# 464414_22-01_Sheet1.net
KiCad netlist of a schematic drawn in Altium Designer
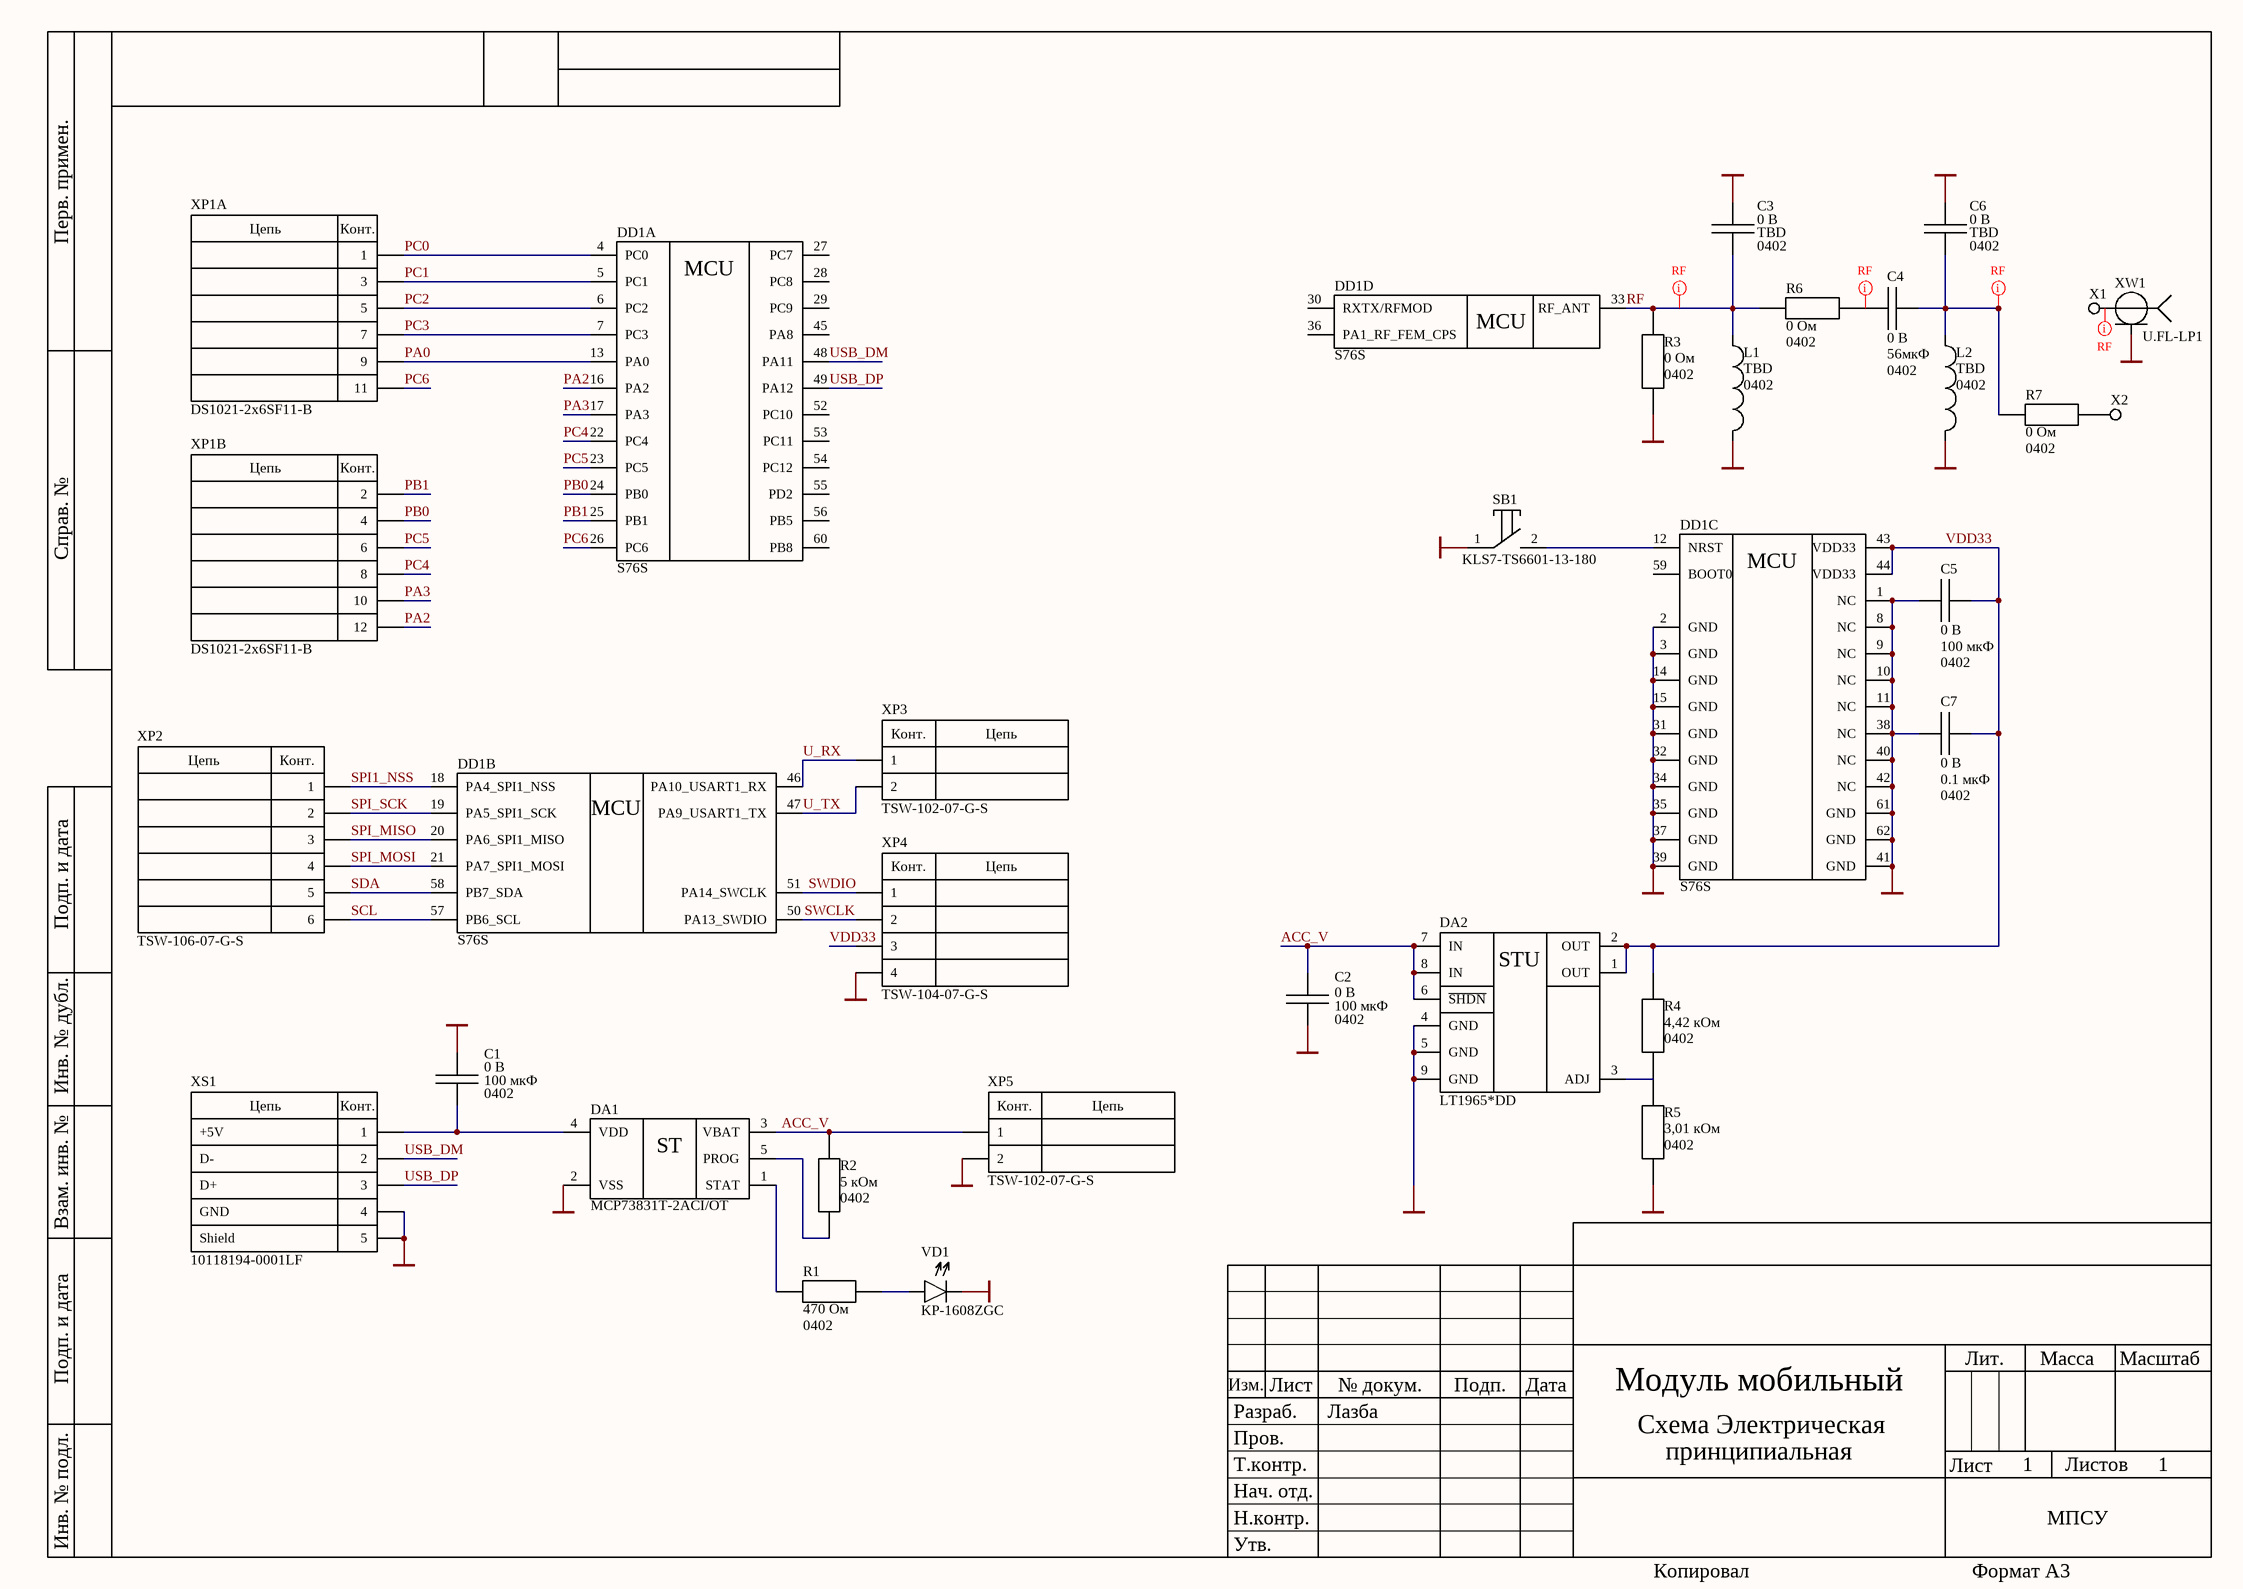
[diagram p0: МПСУ.464414.22-01 Sheet1.SchDoc]

(export (version "E")
  (design (tool "Eeschema 10.0.6"))
  (components
    (comp (ref "C1")
      (value "100 мкФ")
      (footprint "Passive_V2_0:CAPC100X50X55L20N")
      (description "Capacitor 0402")
      (fields
        (field (name "TOLERANCE") "0 %")
        (field (name "PEAK_CONDITION") "0 В")
        (field (name "PACKAGE") "0402")
        (field (name "Comment") "100 мкФ ± 0 % 0 В  0402 ")
        (field (name "DESIGNER") "Свидерский")
      )
      (libsource (lib "Passive_V2_0") (part "C 0402"))
    )
    (comp (ref "C2")
      (value "100 мкФ")
      (footprint "Passive_V2_0:CAPC100X50X55L20N")
      (description "Capacitor 0402")
      (fields
        (field (name "TOLERANCE") "0 %")
        (field (name "PEAK_CONDITION") "0 В")
        (field (name "PACKAGE") "0402")
        (field (name "Comment") "100 мкФ ± 0 % 0 В  0402 ")
        (field (name "DESIGNER") "Свидерский")
      )
      (libsource (lib "Passive_V2_0") (part "C 0402"))
    )
    (comp (ref "C3")
      (value "TBD")
      (footprint "Passive_V2_0:CAPC100X50X55L20N")
      (description "Capacitor 0402")
      (fields
        (field (name "TOLERANCE") "0 %")
        (field (name "PEAK_CONDITION") "0 В")
        (field (name "PACKAGE") "0402")
        (field (name "Comment") "TBD ± 0 % 0 В  0402 ")
        (field (name "DESIGNER") "Свидерский")
      )
      (libsource (lib "Passive_V2_0") (part "C 0402"))
    )
    (comp (ref "C4")
      (value "56мкФ")
      (footprint "Passive_V2_0:CAPC100X50X55L20N")
      (description "Capacitor 0402")
      (fields
        (field (name "TOLERANCE") "0 %")
        (field (name "PEAK_CONDITION") "0 В")
        (field (name "PACKAGE") "0402")
        (field (name "Comment") "56мкФ ± 0 % 0 В  0402 ")
        (field (name "DESIGNER") "Свидерский")
      )
      (libsource (lib "Passive_V2_0") (part "C 0402"))
    )
    (comp (ref "C5")
      (value "100 мкФ")
      (footprint "Passive_V2_0:CAPC100X50X55L20N")
      (description "Capacitor 0402")
      (fields
        (field (name "TOLERANCE") "0 %")
        (field (name "PEAK_CONDITION") "0 В")
        (field (name "PACKAGE") "0402")
        (field (name "Comment") "100 мкФ ± 0 % 0 В  0402 ")
        (field (name "DESIGNER") "Свидерский")
      )
      (libsource (lib "Passive_V2_0") (part "C 0402"))
    )
    (comp (ref "C6")
      (value "TBD")
      (footprint "Passive_V2_0:CAPC100X50X55L20N")
      (description "Capacitor 0402")
      (fields
        (field (name "TOLERANCE") "0 %")
        (field (name "PEAK_CONDITION") "0 В")
        (field (name "PACKAGE") "0402")
        (field (name "Comment") "TBD ± 0 % 0 В  0402 ")
        (field (name "DESIGNER") "Свидерский")
      )
      (libsource (lib "Passive_V2_0") (part "C 0402"))
    )
    (comp (ref "C7")
      (value "0.1 мкФ")
      (footprint "Passive_V2_0:CAPC100X50X55L20N")
      (description "Capacitor 0402")
      (fields
        (field (name "TOLERANCE") "0 %")
        (field (name "PEAK_CONDITION") "0 В")
        (field (name "PACKAGE") "0402")
        (field (name "Comment") "0.1 мкФ ± 0 % 0 В  0402 ")
        (field (name "DESIGNER") "Свидерский")
      )
      (libsource (lib "Passive_V2_0") (part "C 0402"))
    )
    (comp (ref "DA1")
      (value "MCP73831T-2ACI/OT")
      (footprint "IC_V2_0:SOTFL95P270X145-5N")
      (description "Miniature Single-Cell, Fully Integrated Li-Ion,\r\nLi-Polymer Charge Management Controllers")
      (fields
        (field (name "MANUFACTURER") "Microchip")
        (field (name "PARTNUMBER") "MCP73831T-2ACI/OT")
        (field (name "DESIGNER") "Лазба")
      )
      (libsource (lib "IC_V2_0") (part "MCP7383*"))
    )
    (comp (ref "DA2")
      (value "LT1965*DD")
      (footprint "IC_V2_0:SON9P50_300X300X80L40X25T244X160N")
      (description "1.1A, Low Noise,  Low Dropout Linear Regulator")
      (fields
        (field (name "MANUFACTURER") "Analog Devices")
        (field (name "PARTNUMBER") "LT1965*DD")
        (field (name "DESIGNER") "Свидерский")
      )
      (libsource (lib "IC_V2_0") (part "LT1965*DD"))
    )
    (comp (ref "DD1")
      (value "DD1")
      (footprint "IC_V2_0:S7XS")
      (fields
        (field (name "MANUFACTURER") "AcSIP")
        (field (name "PARTNUMBER") "S76S")
        (field (name "DESIGNER") "Лазба")
      )
      (libsource (lib "") (part "S76S_1"))
    )
    (comp (ref "L1")
      (value "TBD")
      (footprint "Passive_V2_0:INDC100X50X60L10N")
      (description "Inductor 0402")
      (fields
        (field (name "TOLERANCE") "0 %")
        (field (name "PACKAGE") "0402")
        (field (name "Comment") "TBD ± 0 % 0 А 0402 ")
        (field (name "DESIGNER") "Свидерский")
      )
      (libsource (lib "Passive_V2_0") (part "L 0402"))
    )
    (comp (ref "L2")
      (value "TBD")
      (footprint "Passive_V2_0:INDC100X50X60L10N")
      (description "Inductor 0402")
      (fields
        (field (name "TOLERANCE") "0 %")
        (field (name "PACKAGE") "0402")
        (field (name "Comment") "TBD ± 0 % 0 А 0402 ")
        (field (name "DESIGNER") "Свидерский")
      )
      (libsource (lib "Passive_V2_0") (part "L 0402"))
    )
    (comp (ref "R1")
      (value "470 Ом")
      (footprint "Passive_V2_0:RESC100X50X40L25N")
      (description "Resistor 0402")
      (fields
        (field (name "TOLERANCE") "0 %")
        (field (name "PACKAGE") "0402")
        (field (name "Comment") "470 Ом ± 0 % 0 Вт 0402 ")
        (field (name "DESIGNER") "Свидерский")
      )
      (libsource (lib "") (part "R 0402_1"))
    )
    (comp (ref "R2")
      (value "5 кОм")
      (footprint "Passive_V2_0:RESC100X50X40L25N")
      (description "Resistor 0402")
      (fields
        (field (name "TOLERANCE") "0 %")
        (field (name "PACKAGE") "0402")
        (field (name "Comment") "5 кОм ± 0 % 0 Вт 0402 ")
        (field (name "DESIGNER") "Свидерский")
      )
      (libsource (lib "") (part "R 0402_2"))
    )
    (comp (ref "R3")
      (value "0 Ом")
      (footprint "Passive_V2_0:RESC100X50X40L25N")
      (description "Resistor 0402")
      (fields
        (field (name "TOLERANCE") "0 %")
        (field (name "PACKAGE") "0402")
        (field (name "Comment") "0 Ом ± 0 % 0 Вт 0402 ")
        (field (name "DESIGNER") "Свидерский")
      )
      (libsource (lib "Passive_V2_0") (part "R 0402"))
    )
    (comp (ref "R4")
      (value "4,42 кОм")
      (footprint "Passive_V2_0:RESC100X50X40L25N")
      (description "Resistor 0402")
      (fields
        (field (name "TOLERANCE") "0 %")
        (field (name "PACKAGE") "0402")
        (field (name "Comment") "4,42 кОм ± 0 % 0 Вт 0402 ")
        (field (name "DESIGNER") "Свидерский")
      )
      (libsource (lib "Passive_V2_0") (part "R 0402"))
    )
    (comp (ref "R5")
      (value "3,01 кОм")
      (footprint "Passive_V2_0:RESC100X50X40L25N")
      (description "Resistor 0402")
      (fields
        (field (name "TOLERANCE") "0 %")
        (field (name "PACKAGE") "0402")
        (field (name "Comment") "3,01 кОм ± 0 % 0 Вт 0402 ")
        (field (name "DESIGNER") "Свидерский")
      )
      (libsource (lib "Passive_V2_0") (part "R 0402"))
    )
    (comp (ref "R6")
      (value "0 Ом")
      (footprint "Passive_V2_0:RESC100X50X40L25N")
      (description "Resistor 0402")
      (fields
        (field (name "TOLERANCE") "0 %")
        (field (name "PACKAGE") "0402")
        (field (name "Comment") "0 Ом ± 0 % 0 Вт 0402 ")
        (field (name "DESIGNER") "Свидерский")
      )
      (libsource (lib "") (part "R 0402_1"))
    )
    (comp (ref "R7")
      (value "0 Ом")
      (footprint "Passive_V2_0:RESC100X50X40L25N")
      (description "Resistor 0402")
      (fields
        (field (name "TOLERANCE") "0 %")
        (field (name "PACKAGE") "0402")
        (field (name "Comment") "0 Ом ± 0 % 0 Вт 0402 ")
        (field (name "DESIGNER") "Свидерский")
      )
      (libsource (lib "") (part "R 0402_1"))
    )
    (comp (ref "SB1")
      (value "~")
      (footprint "Passive_V2_0:KLS7-TS6601")
      (description "6x6 Tact Switch Series")
      (fields
        (field (name "MANUFACTURER") "KLS electronic co ltd")
        (field (name "PARTNUMBER") "KLS7-TS6601-13-180")
        (field (name "DESIGNER") "Лазба")
      )
      (libsource (lib "Passive_V2_0") (part "KLS7-TS6601*"))
    )
    (comp (ref "VD1")
      (value "KP-1608ZGC")
      (footprint "Discrete_V2_0:KP-1608ZGC")
      (description "1.6X0.8mm SMD CHIP LED LAMP")
      (fields
        (field (name "MANUFACTURER") "Kingbright")
        (field (name "PARTNUMBER") "KP-1608ZGC")
        (field (name "DESIGNER") "Ушакова")
      )
      (libsource (lib "Discrete_V2_0") (part "KP-1608***"))
    )
    (comp (ref "X1")
      (value "Contact Pad")
      (footprint "Primitive_V2_0:Contact_Pad 0.55x0.55")
      (description "Контактная площадка (1,5 х 1,5 мм) для запайки провода")
      (fields (field (name "DESIGNER") "Свидерский"))
      (libsource (lib "Primitive_V2_0") (part "Contact Pad"))
    )
    (comp (ref "X2")
      (value "Contact Pad")
      (footprint "Primitive_V2_0:Contact_Pad 0.55x0.55")
      (description "Контактная площадка (1,5 х 1,5 мм) для запайки провода")
      (fields (field (name "DESIGNER") "Свидерский"))
      (libsource (lib "Primitive_V2_0") (part "Contact Pad"))
    )
    (comp (ref "XP1")
      (value "DS1021-2x6SF11-B")
      (footprint "Connectors_V2_0:HDRV12W64P254_6X2_1524X508H600")
      (description "Вилка 2,54мм")
      (fields
        (field (name "MANUFACTURER") "Connfly Electronic")
        (field (name "PARTNUMBER") "DS1021-2x6SF11-B")
        (field (name "DESIGNER") "Свидерский")
      )
      (libsource (lib "Connectors_V2_0") (part "DS1021-2x6SF11-B"))
    )
    (comp (ref "XP2")
      (value "TSW-106-07-G-S")
      (footprint "Connectors_V2_0:TSW-106-07-G-S")
      (description "Вилка 2,54 мм")
      (fields
        (field (name "MANUFACTURER") "Samtec")
        (field (name "PARTNUMBER") "TSW-106-07-G-S")
        (field (name "DESIGNER") "Лазба")
      )
      (libsource (lib "Connectors_V2_0") (part "TSW-106-07-G-S"))
    )
    (comp (ref "XP3")
      (value "TSW-102-07-G-S")
      (footprint "Connectors_V2_0:TSW-102-07-G-S")
      (description "2x1 Вилка 2,54 мм")
      (fields
        (field (name "MANUFACTURER") "Samtec")
        (field (name "PARTNUMBER") "TSW-102-07-G-S")
        (field (name "DESIGNER") "Погорельский")
      )
      (libsource (lib "Connectors_V2_0") (part "TSW-102-07-G-S"))
    )
    (comp (ref "XP4")
      (value "TSW-104-07-G-S")
      (footprint "Connectors_V2_0:TSW-104-07-G-S")
      (description "Вилка 2,54 мм")
      (fields
        (field (name "MANUFACTURER") "Samtec")
        (field (name "PARTNUMBER") "TSW-104-07-G-S")
        (field (name "DESIGNER") "Затонская")
      )
      (libsource (lib "Connectors_V2_0") (part "TSW-104-07-G-S"))
    )
    (comp (ref "XP5")
      (value "TSW-102-07-G-S")
      (footprint "Connectors_V2_0:TSW-102-07-G-S")
      (description "2x1 Вилка 2,54 мм")
      (fields
        (field (name "MANUFACTURER") "Samtec")
        (field (name "PARTNUMBER") "TSW-102-07-G-S")
        (field (name "DESIGNER") "Погорельский")
      )
      (libsource (lib "Connectors_V2_0") (part "TSW-102-07-G-S"))
    )
    (comp (ref "XS1")
      (value "10118194-0001LF")
      (footprint "Connectors_V2_0:micro_USB_TH")
      (description "micro USB, Through Hole Mount")
      (fields
        (field (name "MANUFACTURER") "Amphenal ICC")
        (field (name "PARTNUMBER") "10118194-0001LF")
        (field (name "DESIGNER") "Свидерский")
      )
      (libsource (lib "Connectors_V2_0") (part "10118194-0001LF"))
    )
    (comp (ref "XW1")
      (value "U.FL-LP1")
      (footprint "Connectors_V2_0:U.FL-LP")
      (description "RF connector, Right Angle Jack PCB SMA Female End Launch Connector")
      (fields
        (field (name "MANUFACTURER") "Hirose Electric")
        (field (name "PARTNUMBER") "U.FL-LP1")
        (field (name "DESIGNER") "Лазба")
      )
      (libsource (lib "Connectors_V2_0") (part "U.FL-R-SMT"))
    )
  )
  (nets
    (net (code "1") (name "/ACC_V") (class "Default")
      (node (ref "C2") (pin "1") (pinfunction "1_1") (pintype "passive"))
      (node (ref "DA1") (pin "3") (pinfunction "VBAT_3") (pintype "passive"))
      (node (ref "DA2") (pin "6") (pinfunction "~{SHDN}_6") (pintype "passive"))
      (node (ref "DA2") (pin "7") (pinfunction "IN_7") (pintype "passive"))
      (node (ref "DA2") (pin "8") (pinfunction "IN_8") (pintype "passive"))
      (node (ref "R2") (pin "2") (pinfunction "2_2") (pintype "passive"))
      (node (ref "XP5") (pin "1") (pinfunction "1_1") (pintype "passive"))
    )
    (net (code "2") (name "/PA0") (class "Default")
      (node (ref "DD1") (pin "13") (pinfunction "PA0_13") (pintype "passive"))
      (node (ref "XP1") (pin "9") (pinfunction "9_9") (pintype "passive"))
    )
    (net (code "3") (name "/PA2") (class "Default")
      (node (ref "DD1") (pin "16") (pinfunction "PA2_16") (pintype "passive"))
      (node (ref "XP1") (pin "12") (pinfunction "12_12") (pintype "passive"))
    )
    (net (code "4") (name "/PA3") (class "Default")
      (node (ref "DD1") (pin "17") (pinfunction "PA3_17") (pintype "passive"))
      (node (ref "XP1") (pin "10") (pinfunction "10_10") (pintype "passive"))
    )
    (net (code "5") (name "/PB0") (class "Default")
      (node (ref "DD1") (pin "24") (pinfunction "PB0_24") (pintype "passive"))
      (node (ref "XP1") (pin "4") (pinfunction "4_4") (pintype "passive"))
    )
    (net (code "6") (name "/PB1") (class "Default")
      (node (ref "DD1") (pin "25") (pinfunction "PB1_25") (pintype "passive"))
      (node (ref "XP1") (pin "2") (pinfunction "2_2") (pintype "passive"))
    )
    (net (code "7") (name "/PC0") (class "Default")
      (node (ref "DD1") (pin "4") (pinfunction "PC0_4") (pintype "passive"))
      (node (ref "XP1") (pin "1") (pinfunction "1_1") (pintype "passive"))
    )
    (net (code "8") (name "/PC1") (class "Default")
      (node (ref "DD1") (pin "5") (pinfunction "PC1_5") (pintype "passive"))
      (node (ref "XP1") (pin "3") (pinfunction "3_3") (pintype "passive"))
    )
    (net (code "9") (name "/PC2") (class "Default")
      (node (ref "DD1") (pin "6") (pinfunction "PC2_6") (pintype "passive"))
      (node (ref "XP1") (pin "5") (pinfunction "5_5") (pintype "passive"))
    )
    (net (code "10") (name "/PC3") (class "Default")
      (node (ref "DD1") (pin "7") (pinfunction "PC3_7") (pintype "passive"))
      (node (ref "XP1") (pin "7") (pinfunction "7_7") (pintype "passive"))
    )
    (net (code "11") (name "/PC4") (class "Default")
      (node (ref "DD1") (pin "22") (pinfunction "PC4_22") (pintype "passive"))
      (node (ref "XP1") (pin "8") (pinfunction "8_8") (pintype "passive"))
    )
    (net (code "12") (name "/PC5") (class "Default")
      (node (ref "DD1") (pin "23") (pinfunction "PC5_23") (pintype "passive"))
      (node (ref "XP1") (pin "6") (pinfunction "6_6") (pintype "passive"))
    )
    (net (code "13") (name "/PC6") (class "Default")
      (node (ref "DD1") (pin "26") (pinfunction "PC6_26") (pintype "passive"))
      (node (ref "XP1") (pin "11") (pinfunction "11_11") (pintype "passive"))
    )
    (net (code "14") (name "/RF") (class "Default")
      (node (ref "C3") (pin "1") (pinfunction "1_1") (pintype "passive"))
      (node (ref "DD1") (pin "33") (pinfunction "RF_ANT_33") (pintype "passive"))
      (node (ref "L1") (pin "1") (pinfunction "1_1") (pintype "passive"))
      (node (ref "R3") (pin "1") (pinfunction "1_1") (pintype "passive"))
      (node (ref "R6") (pin "1") (pinfunction "1_1") (pintype "passive"))
    )
    (net (code "15") (name "/SCL") (class "Default")
      (node (ref "DD1") (pin "57") (pinfunction "PB6_SCL_57") (pintype "passive"))
      (node (ref "XP2") (pin "6") (pinfunction "6_6") (pintype "passive"))
    )
    (net (code "16") (name "/SDA") (class "Default")
      (node (ref "DD1") (pin "58") (pinfunction "PB7_SDA_58") (pintype "passive"))
      (node (ref "XP2") (pin "5") (pinfunction "5_5") (pintype "passive"))
    )
    (net (code "17") (name "/SPI1_NSS") (class "Default")
      (node (ref "DD1") (pin "18") (pinfunction "PA4_SPI1_NSS_18") (pintype "passive"))
      (node (ref "XP2") (pin "1") (pinfunction "1_1") (pintype "passive"))
    )
    (net (code "18") (name "/SPI_MISO") (class "Default")
      (node (ref "DD1") (pin "20") (pinfunction "PA6_SPI1_MISO_20") (pintype "passive"))
      (node (ref "XP2") (pin "3") (pinfunction "3_3") (pintype "passive"))
    )
    (net (code "19") (name "/SPI_MOSI") (class "Default")
      (node (ref "DD1") (pin "21") (pinfunction "PA7_SPI1_MOSI_21") (pintype "passive"))
      (node (ref "XP2") (pin "4") (pinfunction "4_4") (pintype "passive"))
    )
    (net (code "20") (name "/SPI_SCK") (class "Default")
      (node (ref "DD1") (pin "19") (pinfunction "PA5_SPI1_SCK_19") (pintype "passive"))
      (node (ref "XP2") (pin "2") (pinfunction "2_2") (pintype "passive"))
    )
    (net (code "21") (name "/SWCLK") (class "Default")
      (node (ref "DD1") (pin "50") (pinfunction "PA13_SWDIO_50") (pintype "passive"))
      (node (ref "XP4") (pin "2") (pinfunction "2_2") (pintype "passive"))
    )
    (net (code "22") (name "/SWDIO") (class "Default")
      (node (ref "DD1") (pin "51") (pinfunction "PA14_SWCLK_51") (pintype "passive"))
      (node (ref "XP4") (pin "1") (pinfunction "1_1") (pintype "passive"))
    )
    (net (code "23") (name "/USB_DM") (class "Default")
      (node (ref "DD1") (pin "48") (pinfunction "PA11_48") (pintype "passive"))
      (node (ref "XS1") (pin "2") (pinfunction "2_2") (pintype "passive"))
    )
    (net (code "24") (name "/USB_DP") (class "Default")
      (node (ref "DD1") (pin "49") (pinfunction "PA12_49") (pintype "passive"))
      (node (ref "XS1") (pin "3") (pinfunction "3_3") (pintype "passive"))
    )
    (net (code "25") (name "/U_RX") (class "Default")
      (node (ref "DD1") (pin "46") (pinfunction "PA10_USART1_RX_46") (pintype "passive"))
      (node (ref "XP3") (pin "1") (pinfunction "1_1") (pintype "passive"))
    )
    (net (code "26") (name "/U_TX") (class "Default")
      (node (ref "DD1") (pin "47") (pinfunction "PA9_USART1_TX_47") (pintype "passive"))
      (node (ref "XP3") (pin "2") (pinfunction "2_2") (pintype "passive"))
    )
    (net (code "27") (name "/VDD33") (class "Default")
      (node (ref "C5") (pin "2") (pinfunction "2_2") (pintype "passive"))
      (node (ref "C7") (pin "1") (pinfunction "1_1") (pintype "passive"))
      (node (ref "DA2") (pin "1") (pinfunction "OUT_1") (pintype "passive"))
      (node (ref "DA2") (pin "2") (pinfunction "OUT_2") (pintype "passive"))
      (node (ref "DD1") (pin "43") (pinfunction "VDD33_43") (pintype "passive"))
      (node (ref "DD1") (pin "44") (pinfunction "VDD33_44") (pintype "passive"))
      (node (ref "R4") (pin "1") (pinfunction "1_1") (pintype "passive"))
      (node (ref "XP4") (pin "3") (pinfunction "3_3") (pintype "passive"))
    )
    (net (code "28") (name "GND") (class "Default")
      (node (ref "C1") (pin "1") (pinfunction "1_1") (pintype "passive"))
      (node (ref "C2") (pin "2") (pinfunction "2_2") (pintype "passive"))
      (node (ref "C3") (pin "2") (pinfunction "2_2") (pintype "passive"))
      (node (ref "C5") (pin "1") (pinfunction "1_1") (pintype "passive"))
      (node (ref "C6") (pin "2") (pinfunction "2_2") (pintype "passive"))
      (node (ref "C7") (pin "2") (pinfunction "2_2") (pintype "passive"))
      (node (ref "DA1") (pin "2") (pinfunction "VSS_2") (pintype "passive"))
      (node (ref "DA2") (pin "4") (pinfunction "GND_4") (pintype "passive"))
      (node (ref "DA2") (pin "5") (pinfunction "GND_5") (pintype "passive"))
      (node (ref "DA2") (pin "9") (pinfunction "GND_9") (pintype "passive"))
      (node (ref "DD1") (pin "1") (pinfunction "NC_1") (pintype "passive"))
      (node (ref "DD1") (pin "10") (pinfunction "NC_10") (pintype "passive"))
      (node (ref "DD1") (pin "11") (pinfunction "NC_11") (pintype "passive"))
      (node (ref "DD1") (pin "14") (pinfunction "GND_14") (pintype "passive"))
      (node (ref "DD1") (pin "15") (pinfunction "GND_15") (pintype "passive"))
      (node (ref "DD1") (pin "2") (pinfunction "GND_2") (pintype "passive"))
      (node (ref "DD1") (pin "3") (pinfunction "GND_3") (pintype "passive"))
      (node (ref "DD1") (pin "31") (pinfunction "GND_31") (pintype "passive"))
      (node (ref "DD1") (pin "32") (pinfunction "GND_32") (pintype "passive"))
      (node (ref "DD1") (pin "34") (pinfunction "GND_34") (pintype "passive"))
      (node (ref "DD1") (pin "35") (pinfunction "GND_35") (pintype "passive"))
      (node (ref "DD1") (pin "37") (pinfunction "GND_37") (pintype "passive"))
      (node (ref "DD1") (pin "38") (pinfunction "NC_38") (pintype "passive"))
      (node (ref "DD1") (pin "39") (pinfunction "GND_39") (pintype "passive"))
      (node (ref "DD1") (pin "40") (pinfunction "NC_40") (pintype "passive"))
      (node (ref "DD1") (pin "41") (pinfunction "GND_41") (pintype "passive"))
      (node (ref "DD1") (pin "42") (pinfunction "NC_42") (pintype "passive"))
      (node (ref "DD1") (pin "61") (pinfunction "GND_61") (pintype "passive"))
      (node (ref "DD1") (pin "62") (pinfunction "GND_62") (pintype "passive"))
      (node (ref "DD1") (pin "8") (pinfunction "NC_8") (pintype "passive"))
      (node (ref "DD1") (pin "9") (pinfunction "NC_9") (pintype "passive"))
      (node (ref "L1") (pin "2") (pinfunction "2_2") (pintype "passive"))
      (node (ref "L2") (pin "2") (pinfunction "2_2") (pintype "passive"))
      (node (ref "R3") (pin "2") (pinfunction "2_2") (pintype "passive"))
      (node (ref "R5") (pin "2") (pinfunction "2_2") (pintype "passive"))
      (node (ref "SB1") (pin "1") (pintype "passive"))
      (node (ref "VD1") (pin "2") (pinfunction "2_2") (pintype "passive"))
      (node (ref "XP4") (pin "4") (pinfunction "4_4") (pintype "passive"))
      (node (ref "XP5") (pin "2") (pinfunction "2_2") (pintype "passive"))
      (node (ref "XS1") (pin "4") (pinfunction "4_4") (pintype "passive"))
      (node (ref "XS1") (pin "5") (pinfunction "5_5") (pintype "passive"))
      (node (ref "XW1") (pin "2") (pinfunction "GND_2") (pintype "passive"))
    )
    (net (code "29") (name "Net-(C4-Pad1)") (class "Default")
      (node (ref "C4") (pin "1") (pinfunction "1_1") (pintype "passive"))
      (node (ref "C6") (pin "1") (pinfunction "1_1") (pintype "passive"))
      (node (ref "L2") (pin "1") (pinfunction "1_1") (pintype "passive"))
      (node (ref "R7") (pin "1") (pinfunction "1_1") (pintype "passive"))
    )
    (net (code "30") (name "Net-(C4-Pad2)") (class "Default")
      (node (ref "C4") (pin "2") (pinfunction "2_2") (pintype "passive"))
      (node (ref "R6") (pin "2") (pinfunction "2_2") (pintype "passive"))
    )
    (net (code "31") (name "Net-(DA1-PROG)") (class "Default")
      (node (ref "DA1") (pin "5") (pinfunction "PROG_5") (pintype "passive"))
      (node (ref "R2") (pin "1") (pinfunction "1_1") (pintype "passive"))
    )
    (net (code "32") (name "Net-(DA1-STAT)") (class "Default")
      (node (ref "DA1") (pin "1") (pinfunction "STAT_1") (pintype "passive"))
      (node (ref "R1") (pin "1") (pinfunction "1_1") (pintype "passive"))
    )
    (net (code "33") (name "Net-(DA1-VDD)") (class "Default")
      (node (ref "C1") (pin "2") (pinfunction "2_2") (pintype "passive"))
      (node (ref "DA1") (pin "4") (pinfunction "VDD_4") (pintype "passive"))
      (node (ref "XS1") (pin "1") (pinfunction "1_1") (pintype "passive"))
    )
    (net (code "34") (name "Net-(DA2-ADJ)") (class "Default")
      (node (ref "DA2") (pin "3") (pinfunction "ADJ_3") (pintype "passive"))
      (node (ref "R4") (pin "2") (pinfunction "2_2") (pintype "passive"))
      (node (ref "R5") (pin "1") (pinfunction "1_1") (pintype "passive"))
    )
    (net (code "35") (name "Net-(DD1C-NRST)") (class "Default")
      (node (ref "DD1") (pin "12") (pinfunction "NRST_12") (pintype "passive"))
      (node (ref "SB1") (pin "2") (pintype "passive"))
    )
    (net (code "36") (name "Net-(R1-Pad2)") (class "Default")
      (node (ref "R1") (pin "2") (pinfunction "2_2") (pintype "passive"))
      (node (ref "VD1") (pin "1") (pinfunction "1_1") (pintype "passive"))
    )
    (net (code "37") (name "Net-(X1-TestPoint)") (class "Default")
      (node (ref "X1") (pin "1") (pinfunction "TestPoint_1") (pintype "passive"))
      (node (ref "XW1") (pin "1") (pinfunction "RF_1") (pintype "passive"))
    )
    (net (code "38") (name "Net-(X2-TestPoint)") (class "Default")
      (node (ref "R7") (pin "2") (pinfunction "2_2") (pintype "passive"))
      (node (ref "X2") (pin "1") (pinfunction "TestPoint_1") (pintype "passive"))
    )
    (net (code "39") (name "unconnected-(DD1A-PA8-Pad45)") (class "Default")
      (node (ref "DD1") (pin "45") (pinfunction "PA8_45") (pintype "passive"))
    )
    (net (code "40") (name "unconnected-(DD1A-PB5-Pad56)") (class "Default")
      (node (ref "DD1") (pin "56") (pinfunction "PB5_56") (pintype "passive"))
    )
    (net (code "41") (name "unconnected-(DD1A-PB8-Pad60)") (class "Default")
      (node (ref "DD1") (pin "60") (pinfunction "PB8_60") (pintype "passive"))
    )
    (net (code "42") (name "unconnected-(DD1A-PC7-Pad27)") (class "Default")
      (node (ref "DD1") (pin "27") (pinfunction "PC7_27") (pintype "passive"))
    )
    (net (code "43") (name "unconnected-(DD1A-PC8-Pad28)") (class "Default")
      (node (ref "DD1") (pin "28") (pinfunction "PC8_28") (pintype "passive"))
    )
    (net (code "44") (name "unconnected-(DD1A-PC9-Pad29)") (class "Default")
      (node (ref "DD1") (pin "29") (pinfunction "PC9_29") (pintype "passive"))
    )
    (net (code "45") (name "unconnected-(DD1A-PC10-Pad52)") (class "Default")
      (node (ref "DD1") (pin "52") (pinfunction "PC10_52") (pintype "passive"))
    )
    (net (code "46") (name "unconnected-(DD1A-PC11-Pad53)") (class "Default")
      (node (ref "DD1") (pin "53") (pinfunction "PC11_53") (pintype "passive"))
    )
    (net (code "47") (name "unconnected-(DD1A-PC12-Pad54)") (class "Default")
      (node (ref "DD1") (pin "54") (pinfunction "PC12_54") (pintype "passive"))
    )
    (net (code "48") (name "unconnected-(DD1A-PD2-Pad55)") (class "Default")
      (node (ref "DD1") (pin "55") (pinfunction "PD2_55") (pintype "passive"))
    )
    (net (code "49") (name "unconnected-(DD1C-BOOT0-Pad59)") (class "Default")
      (node (ref "DD1") (pin "59") (pinfunction "BOOT0_59") (pintype "passive"))
    )
    (net (code "50") (name "unconnected-(DD1D-PA1_RF_FEM_CPS-Pad36)") (class "Default")
      (node (ref "DD1") (pin "36") (pinfunction "PA1_RF_FEM_CPS_36") (pintype "passive"))
    )
    (net (code "51") (name "unconnected-(DD1D-RXTX{slash}RFMOD-Pad30)") (class "Default")
      (node (ref "DD1") (pin "30") (pinfunction "RXTX/RFMOD_30") (pintype "passive"))
    )
  )
)
